# powerDist.net
KiCad netlist of a schematic drawn in EAGLE
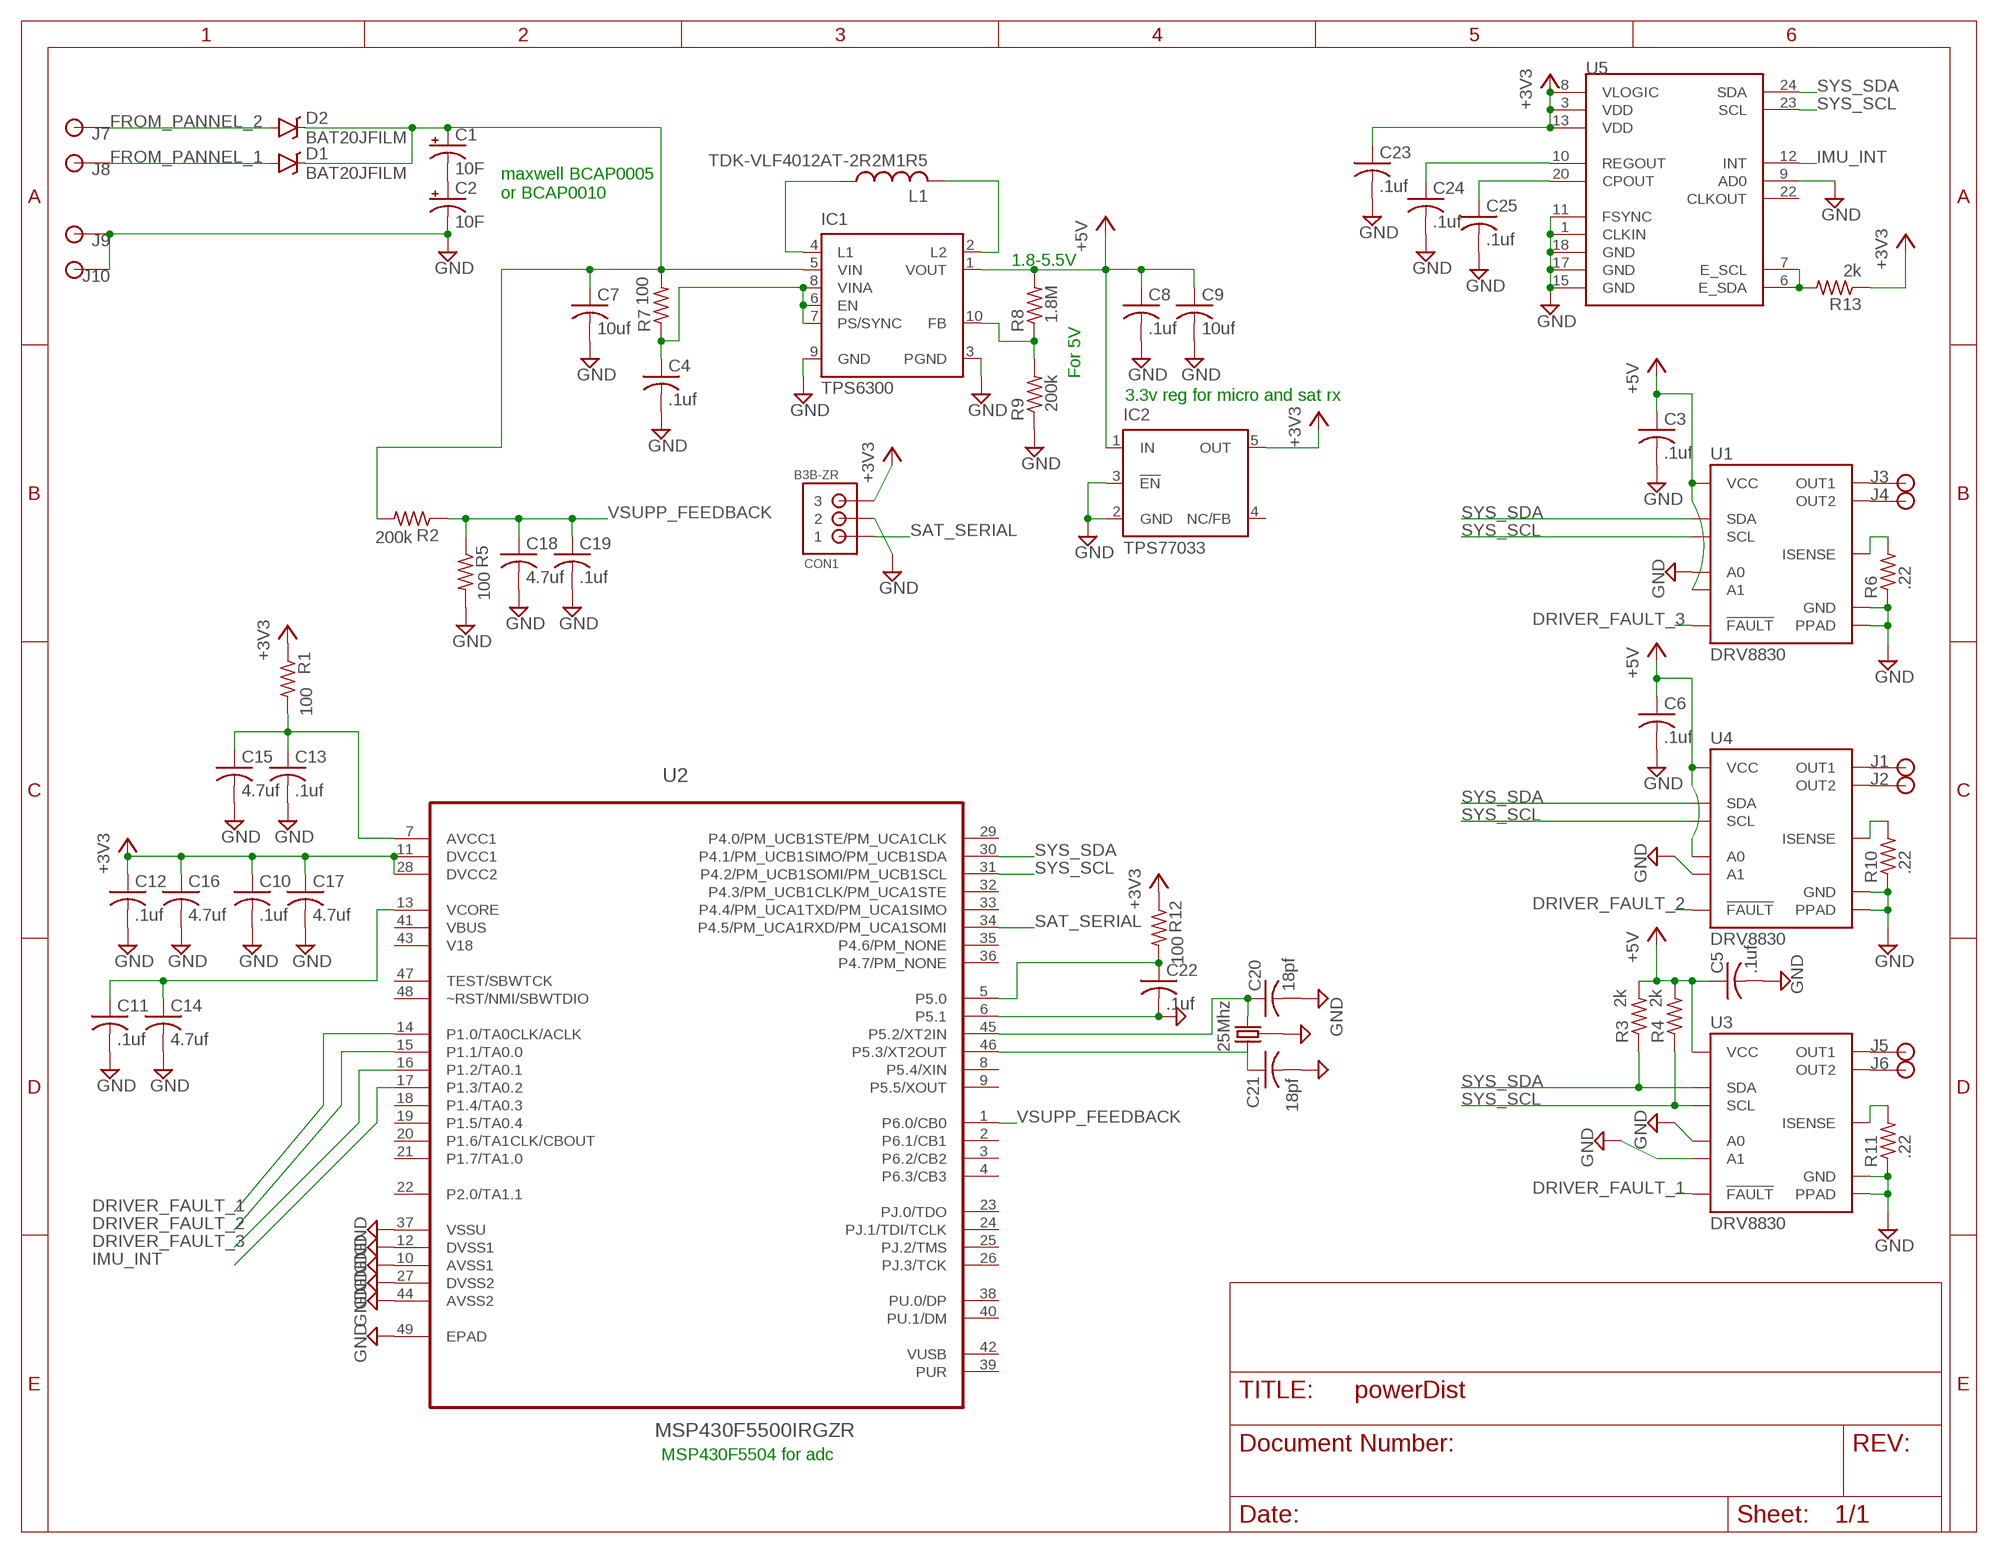
[diagram p0: schematic, sheet 1]

(export (version "E")
  (design (tool "Eeschema 10.0.6"))
  (components
    (comp (ref "C1")
      (value "10F")
      (footprint "eagle-import:E5-10,5")
      (libsource (lib "eagle-import") (part "CPOL-USE5-10.5"))
    )
    (comp (ref "C2")
      (value "10F")
      (footprint "eagle-import:E5-10,5")
      (libsource (lib "eagle-import") (part "CPOL-USE5-10.5"))
    )
    (comp (ref "C3")
      (value ".1uf")
      (footprint "eagle-import:C0603")
      (libsource (lib "eagle-import") (part "C-USC0603"))
    )
    (comp (ref "C4")
      (value ".1uf")
      (footprint "eagle-import:C0603")
      (libsource (lib "eagle-import") (part "C-USC0603"))
    )
    (comp (ref "C5")
      (value ".1uf")
      (footprint "eagle-import:C0603")
      (libsource (lib "eagle-import") (part "C-USC0603"))
    )
    (comp (ref "C6")
      (value ".1uf")
      (footprint "eagle-import:C0603")
      (libsource (lib "eagle-import") (part "C-USC0603"))
    )
    (comp (ref "C7")
      (value "10uf")
      (footprint "eagle-import:C0603")
      (libsource (lib "eagle-import") (part "C-USC0603"))
    )
    (comp (ref "C8")
      (value ".1uf")
      (footprint "eagle-import:C0603")
      (libsource (lib "eagle-import") (part "C-USC0603"))
    )
    (comp (ref "C9")
      (value "10uf")
      (footprint "eagle-import:C0603")
      (libsource (lib "eagle-import") (part "C-USC0603"))
    )
    (comp (ref "C10")
      (value ".1uf")
      (footprint "eagle-import:C0603")
      (libsource (lib "eagle-import") (part "C-USC0603"))
    )
    (comp (ref "C11")
      (value ".1uf")
      (footprint "eagle-import:C0603")
      (libsource (lib "eagle-import") (part "C-USC0603"))
    )
    (comp (ref "C12")
      (value ".1uf")
      (footprint "eagle-import:C0603")
      (libsource (lib "eagle-import") (part "C-USC0603"))
    )
    (comp (ref "C13")
      (value ".1uf")
      (footprint "eagle-import:C0603")
      (libsource (lib "eagle-import") (part "C-USC0603"))
    )
    (comp (ref "C14")
      (value "4.7uf")
      (footprint "eagle-import:C0603")
      (libsource (lib "eagle-import") (part "C-USC0603"))
    )
    (comp (ref "C15")
      (value "4.7uf")
      (footprint "eagle-import:C0603")
      (libsource (lib "eagle-import") (part "C-USC0603"))
    )
    (comp (ref "C16")
      (value "4.7uf")
      (footprint "eagle-import:C0603")
      (libsource (lib "eagle-import") (part "C-USC0603"))
    )
    (comp (ref "C17")
      (value "4.7uf")
      (footprint "eagle-import:C0603")
      (libsource (lib "eagle-import") (part "C-USC0603"))
    )
    (comp (ref "C18")
      (value "4.7uf")
      (footprint "eagle-import:C0603")
      (libsource (lib "eagle-import") (part "C-USC0603"))
    )
    (comp (ref "C19")
      (value ".1uf")
      (footprint "eagle-import:C0603")
      (libsource (lib "eagle-import") (part "C-USC0603"))
    )
    (comp (ref "C20")
      (value "18pf")
      (footprint "eagle-import:C0603")
      (libsource (lib "eagle-import") (part "C-USC0603"))
    )
    (comp (ref "C21")
      (value "18pf")
      (footprint "eagle-import:C0603")
      (libsource (lib "eagle-import") (part "C-USC0603"))
    )
    (comp (ref "C22")
      (value ".1uf")
      (footprint "eagle-import:C0603")
      (libsource (lib "eagle-import") (part "C-USC0603"))
    )
    (comp (ref "C23")
      (value ".1uf")
      (footprint "eagle-import:C0603")
      (libsource (lib "eagle-import") (part "C-USC0603"))
    )
    (comp (ref "C24")
      (value ".1uf")
      (footprint "eagle-import:C0603")
      (libsource (lib "eagle-import") (part "C-USC0603"))
    )
    (comp (ref "C25")
      (value ".1uf")
      (footprint "eagle-import:C0603")
      (libsource (lib "eagle-import") (part "C-USC0603"))
    )
    (comp (ref "CON1")
      (value "B3B-ZR")
      (footprint "eagle-import:B3B-ZR")
      (libsource (lib "eagle-import") (part "B3B-ZR"))
    )
    (comp (ref "D1")
      (value "BAT20JFILM")
      (footprint "eagle-import:SOD-323")
      (libsource (lib "eagle-import") (part "BAT20JFILM"))
    )
    (comp (ref "D2")
      (value "BAT20JFILM")
      (footprint "eagle-import:SOD-323")
      (libsource (lib "eagle-import") (part "BAT20JFILM"))
    )
    (comp (ref "IC1")
      (value "TPS6300")
      (footprint "eagle-import:DRC-S-PVSON-N10")
      (fields (field (name "MPN") "TPS63000DRCTG4"))
      (libsource (lib "eagle-import") (part "TPS6300"))
    )
    (comp (ref "IC2")
      (value "TPS77033")
      (footprint "eagle-import:SOT23-DBV")
      (fields (field (name "MF") "TEXAS INSTRUMENTS") (field (name "MPN") "TPS77033DBVT"))
      (libsource (lib "eagle-import") (part "TPS77033"))
    )
    (comp (ref "J1")
      (value "2MMPAD")
      (footprint "eagle-import:2MMPAD")
      (libsource (lib "eagle-import") (part "2MMPAD"))
    )
    (comp (ref "J2")
      (value "2MMPAD")
      (footprint "eagle-import:2MMPAD")
      (libsource (lib "eagle-import") (part "2MMPAD"))
    )
    (comp (ref "J3")
      (value "2MMPAD")
      (footprint "eagle-import:2MMPAD")
      (libsource (lib "eagle-import") (part "2MMPAD"))
    )
    (comp (ref "J4")
      (value "2MMPAD")
      (footprint "eagle-import:2MMPAD")
      (libsource (lib "eagle-import") (part "2MMPAD"))
    )
    (comp (ref "J5")
      (value "2MMPAD")
      (footprint "eagle-import:2MMPAD")
      (libsource (lib "eagle-import") (part "2MMPAD"))
    )
    (comp (ref "J6")
      (value "2MMPAD")
      (footprint "eagle-import:2MMPAD")
      (libsource (lib "eagle-import") (part "2MMPAD"))
    )
    (comp (ref "J7")
      (value "2MMPAD")
      (footprint "eagle-import:2MMPAD")
      (libsource (lib "eagle-import") (part "2MMPAD"))
    )
    (comp (ref "J8")
      (value "2MMPAD")
      (footprint "eagle-import:2MMPAD")
      (libsource (lib "eagle-import") (part "2MMPAD"))
    )
    (comp (ref "J9")
      (value "2MMPAD")
      (footprint "eagle-import:2MMPAD")
      (libsource (lib "eagle-import") (part "2MMPAD"))
    )
    (comp (ref "J10")
      (value "2MMPAD")
      (footprint "eagle-import:2MMPAD")
      (libsource (lib "eagle-import") (part "2MMPAD"))
    )
    (comp (ref "L1")
      (value "TDK-VLF4012AT-2R2M1R5")
      (footprint "eagle-import:TDK-VLF4012AT-2R2M1R5")
      (fields (field (name "MFG") "TDK"))
      (libsource (lib "eagle-import") (part "TDK-VLF4012AT-2R2M1R5"))
    )
    (comp (ref "Q1")
      (value "25Mhz")
      (footprint "eagle-import:CRYSTAL-SMD-5X3")
      (libsource (lib "eagle-import") (part "CRYSTAL-GROUNDED"))
    )
    (comp (ref "R1")
      (value "100")
      (footprint "eagle-import:R0402")
      (libsource (lib "eagle-import") (part "R-US_R0402"))
    )
    (comp (ref "R2")
      (value "200k")
      (footprint "eagle-import:R0402")
      (libsource (lib "eagle-import") (part "R-US_R0402"))
    )
    (comp (ref "R3")
      (value "2k")
      (footprint "eagle-import:R0402")
      (libsource (lib "eagle-import") (part "R-US_R0402"))
    )
    (comp (ref "R4")
      (value "2k")
      (footprint "eagle-import:R0402")
      (libsource (lib "eagle-import") (part "R-US_R0402"))
    )
    (comp (ref "R5")
      (value "100")
      (footprint "eagle-import:R0402")
      (libsource (lib "eagle-import") (part "R-US_R0402"))
    )
    (comp (ref "R6")
      (value ".22")
      (footprint "eagle-import:R0402")
      (libsource (lib "eagle-import") (part "R-US_R0402"))
    )
    (comp (ref "R7")
      (value "100")
      (footprint "eagle-import:R0402")
      (libsource (lib "eagle-import") (part "R-US_R0402"))
    )
    (comp (ref "R8")
      (value "1.8M")
      (footprint "eagle-import:R0402")
      (libsource (lib "eagle-import") (part "R-US_R0402"))
    )
    (comp (ref "R9")
      (value "200k")
      (footprint "eagle-import:R0402")
      (libsource (lib "eagle-import") (part "R-US_R0402"))
    )
    (comp (ref "R10")
      (value ".22")
      (footprint "eagle-import:R0402")
      (libsource (lib "eagle-import") (part "R-US_R0402"))
    )
    (comp (ref "R11")
      (value ".22")
      (footprint "eagle-import:R0402")
      (libsource (lib "eagle-import") (part "R-US_R0402"))
    )
    (comp (ref "R12")
      (value "100")
      (footprint "eagle-import:R0402")
      (libsource (lib "eagle-import") (part "R-US_R0402"))
    )
    (comp (ref "R13")
      (value "2k")
      (footprint "eagle-import:R0402")
      (libsource (lib "eagle-import") (part "R-US_R0402"))
    )
    (comp (ref "U1")
      (value "DRV8830")
      (footprint "eagle-import:MSOP-10-GNDPAD")
      (libsource (lib "eagle-import") (part "DRV8830"))
    )
    (comp (ref "U2")
      (value "MSP430F5500IRGZR")
      (footprint "eagle-import:QFN50P700X700X100-49N")
      (libsource (lib "eagle-import") (part "MSP430F5500IRGZR"))
    )
    (comp (ref "U3")
      (value "DRV8830")
      (footprint "eagle-import:MSOP-10-GNDPAD")
      (libsource (lib "eagle-import") (part "DRV8830"))
    )
    (comp (ref "U4")
      (value "DRV8830")
      (footprint "eagle-import:MSOP-10-GNDPAD")
      (libsource (lib "eagle-import") (part "DRV8830"))
    )
    (comp (ref "U5")
      (value "MPU-9150QFN-24-NP")
      (footprint "eagle-import:QFN-24-NP")
      (libsource (lib "eagle-import") (part "MPU-9150QFN-24-NP"))
    )
  )
  (nets
    (net (code "1") (name "+3V3") (class "Default")
      (node (ref "C10") (pin "1") (pinfunction "1_1") (pintype "passive"))
      (node (ref "C12") (pin "1") (pinfunction "1_1") (pintype "passive"))
      (node (ref "C16") (pin "1") (pinfunction "1_1") (pintype "passive"))
      (node (ref "C17") (pin "1") (pinfunction "1_1") (pintype "passive"))
      (node (ref "C23") (pin "1") (pinfunction "1_1") (pintype "passive"))
      (node (ref "CON1") (pin "3") (pinfunction "3_3") (pintype "bidirectional"))
      (node (ref "IC2") (pin "5") (pinfunction "OUT_5") (pintype "passive"))
      (node (ref "R1") (pin "1") (pinfunction "1_1") (pintype "passive"))
      (node (ref "R12") (pin "1") (pinfunction "1_1") (pintype "passive"))
      (node (ref "R13") (pin "1") (pinfunction "1_1") (pintype "passive"))
      (node (ref "U2") (pin "11") (pinfunction "DVCC1_11") (pintype "power_in"))
      (node (ref "U2") (pin "28") (pinfunction "DVCC2_28") (pintype "power_in"))
      (node (ref "U5") (pin "13") (pinfunction "VDD_13") (pintype "bidirectional"))
      (node (ref "U5") (pin "3") (pinfunction "VDD_3") (pintype "bidirectional"))
      (node (ref "U5") (pin "8") (pinfunction "VLOGIC_8") (pintype "bidirectional"))
    )
    (net (code "2") (name "+5V") (class "Default")
      (node (ref "C3") (pin "1") (pinfunction "1_1") (pintype "passive"))
      (node (ref "C5") (pin "1") (pinfunction "1_1") (pintype "passive"))
      (node (ref "C6") (pin "1") (pinfunction "1_1") (pintype "passive"))
      (node (ref "C8") (pin "1") (pinfunction "1_1") (pintype "passive"))
      (node (ref "C9") (pin "1") (pinfunction "1_1") (pintype "passive"))
      (node (ref "IC1") (pin "1") (pinfunction "VOUT_1") (pintype "output"))
      (node (ref "IC2") (pin "1") (pinfunction "IN_1") (pintype "input"))
      (node (ref "R3") (pin "2") (pinfunction "2_2") (pintype "passive"))
      (node (ref "R4") (pin "2") (pinfunction "2_2") (pintype "passive"))
      (node (ref "R8") (pin "2") (pinfunction "2_2") (pintype "passive"))
      (node (ref "U1") (pin "4") (pinfunction "VCC_4") (pintype "power_in"))
      (node (ref "U1") (pin "8") (pinfunction "A1_8") (pintype "input"))
      (node (ref "U3") (pin "4") (pinfunction "VCC_4") (pintype "power_in"))
      (node (ref "U4") (pin "4") (pinfunction "VCC_4") (pintype "power_in"))
      (node (ref "U4") (pin "7") (pinfunction "A0_7") (pintype "input"))
    )
    (net (code "3") (name "/DRIVER_FAULT_1") (class "Default")
      (node (ref "U2") (pin "14") (pinfunction "P1.0/TA0CLK/ACLK_14") (pintype "bidirectional"))
      (node (ref "U3") (pin "6") (pinfunction "~{FAULT}_6") (pintype "output"))
    )
    (net (code "4") (name "/DRIVER_FAULT_2") (class "Default")
      (node (ref "U2") (pin "15") (pinfunction "P1.1/TA0.0_15") (pintype "bidirectional"))
      (node (ref "U4") (pin "6") (pinfunction "~{FAULT}_6") (pintype "output"))
    )
    (net (code "5") (name "/DRIVER_FAULT_3") (class "Default")
      (node (ref "U1") (pin "6") (pinfunction "~{FAULT}_6") (pintype "output"))
      (node (ref "U2") (pin "16") (pinfunction "P1.2/TA0.1_16") (pintype "bidirectional"))
    )
    (net (code "6") (name "/FROM_PANNEL_1") (class "Default")
      (node (ref "D1") (pin "A") (pinfunction "A_A") (pintype "passive"))
      (node (ref "J8") (pin "P$1") (pinfunction "P$1_P$1") (pintype "bidirectional"))
    )
    (net (code "7") (name "/FROM_PANNEL_2") (class "Default")
      (node (ref "D2") (pin "A") (pinfunction "A_A") (pintype "passive"))
      (node (ref "J7") (pin "P$1") (pinfunction "P$1_P$1") (pintype "bidirectional"))
    )
    (net (code "8") (name "/IMU_INT") (class "Default")
      (node (ref "U2") (pin "17") (pinfunction "P1.3/TA0.2_17") (pintype "bidirectional"))
      (node (ref "U5") (pin "12") (pinfunction "INT_12") (pintype "bidirectional"))
    )
    (net (code "9") (name "/SAT_SERIAL") (class "Default")
      (node (ref "CON1") (pin "1") (pinfunction "1_1") (pintype "bidirectional"))
      (node (ref "U2") (pin "34") (pinfunction "P4.5/PM_UCA1RXD/PM_UCA1SOMI_34") (pintype "bidirectional"))
    )
    (net (code "10") (name "/SYS_SCL") (class "Default")
      (node (ref "R4") (pin "1") (pinfunction "1_1") (pintype "passive"))
      (node (ref "U1") (pin "10") (pinfunction "SCL_10") (pintype "input"))
      (node (ref "U2") (pin "31") (pinfunction "P4.2/PM_UCB1SOMI/PM_UCB1SCL_31") (pintype "bidirectional"))
      (node (ref "U3") (pin "10") (pinfunction "SCL_10") (pintype "input"))
      (node (ref "U4") (pin "10") (pinfunction "SCL_10") (pintype "input"))
      (node (ref "U5") (pin "23") (pinfunction "SCL_23") (pintype "bidirectional"))
    )
    (net (code "11") (name "/SYS_SDA") (class "Default")
      (node (ref "R3") (pin "1") (pinfunction "1_1") (pintype "passive"))
      (node (ref "U1") (pin "9") (pinfunction "SDA_9") (pintype "bidirectional"))
      (node (ref "U2") (pin "30") (pinfunction "P4.1/PM_UCB1SIMO/PM_UCB1SDA_30") (pintype "bidirectional"))
      (node (ref "U3") (pin "9") (pinfunction "SDA_9") (pintype "bidirectional"))
      (node (ref "U4") (pin "9") (pinfunction "SDA_9") (pintype "bidirectional"))
      (node (ref "U5") (pin "24") (pinfunction "SDA_24") (pintype "bidirectional"))
    )
    (net (code "12") (name "/V18") (class "Default")
      (node (ref "U2") (pin "43") (pinfunction "V18_43") (pintype "power_in"))
    )
    (net (code "13") (name "/VSUPP_FEEDBACK") (class "Default")
      (node (ref "C18") (pin "1") (pinfunction "1_1") (pintype "passive"))
      (node (ref "C19") (pin "1") (pinfunction "1_1") (pintype "passive"))
      (node (ref "R2") (pin "1") (pinfunction "1_1") (pintype "passive"))
      (node (ref "R5") (pin "1") (pinfunction "1_1") (pintype "passive"))
      (node (ref "U2") (pin "1") (pinfunction "P6.0/CB0_1") (pintype "bidirectional"))
    )
    (net (code "14") (name "GND") (class "Default")
      (node (ref "C10") (pin "2") (pinfunction "2_2") (pintype "passive"))
      (node (ref "C11") (pin "2") (pinfunction "2_2") (pintype "passive"))
      (node (ref "C12") (pin "2") (pinfunction "2_2") (pintype "passive"))
      (node (ref "C13") (pin "2") (pinfunction "2_2") (pintype "passive"))
      (node (ref "C14") (pin "2") (pinfunction "2_2") (pintype "passive"))
      (node (ref "C15") (pin "2") (pinfunction "2_2") (pintype "passive"))
      (node (ref "C16") (pin "2") (pinfunction "2_2") (pintype "passive"))
      (node (ref "C17") (pin "2") (pinfunction "2_2") (pintype "passive"))
      (node (ref "C18") (pin "2") (pinfunction "2_2") (pintype "passive"))
      (node (ref "C19") (pin "2") (pinfunction "2_2") (pintype "passive"))
      (node (ref "C2") (pin "-") (pinfunction "-_-") (pintype "passive"))
      (node (ref "C20") (pin "2") (pinfunction "2_2") (pintype "passive"))
      (node (ref "C21") (pin "2") (pinfunction "2_2") (pintype "passive"))
      (node (ref "C22") (pin "2") (pinfunction "2_2") (pintype "passive"))
      (node (ref "C23") (pin "2") (pinfunction "2_2") (pintype "passive"))
      (node (ref "C24") (pin "2") (pinfunction "2_2") (pintype "passive"))
      (node (ref "C25") (pin "2") (pinfunction "2_2") (pintype "passive"))
      (node (ref "C3") (pin "2") (pinfunction "2_2") (pintype "passive"))
      (node (ref "C4") (pin "2") (pinfunction "2_2") (pintype "passive"))
      (node (ref "C5") (pin "2") (pinfunction "2_2") (pintype "passive"))
      (node (ref "C6") (pin "2") (pinfunction "2_2") (pintype "passive"))
      (node (ref "C7") (pin "2") (pinfunction "2_2") (pintype "passive"))
      (node (ref "C8") (pin "2") (pinfunction "2_2") (pintype "passive"))
      (node (ref "C9") (pin "2") (pinfunction "2_2") (pintype "passive"))
      (node (ref "CON1") (pin "2") (pinfunction "2_2") (pintype "bidirectional"))
      (node (ref "IC1") (pin "3") (pinfunction "PGND_3") (pintype "power_in"))
      (node (ref "IC1") (pin "9") (pinfunction "GND_9") (pintype "power_in"))
      (node (ref "IC2") (pin "2") (pinfunction "GND_2") (pintype "power_in"))
      (node (ref "IC2") (pin "3") (pinfunction "~{EN}_3") (pintype "input"))
      (node (ref "J10") (pin "P$1") (pinfunction "P$1_P$1") (pintype "bidirectional"))
      (node (ref "J9") (pin "P$1") (pinfunction "P$1_P$1") (pintype "bidirectional"))
      (node (ref "Q1") (pin "2") (pinfunction "3_2") (pintype "passive"))
      (node (ref "Q1") (pin "4") (pinfunction "3_4") (pintype "passive"))
      (node (ref "R10") (pin "1") (pinfunction "1_1") (pintype "passive"))
      (node (ref "R11") (pin "1") (pinfunction "1_1") (pintype "passive"))
      (node (ref "R5") (pin "2") (pinfunction "2_2") (pintype "passive"))
      (node (ref "R6") (pin "1") (pinfunction "1_1") (pintype "passive"))
      (node (ref "R9") (pin "1") (pinfunction "1_1") (pintype "passive"))
      (node (ref "U1") (pin "5") (pinfunction "GND_5") (pintype "power_in"))
      (node (ref "U1") (pin "7") (pinfunction "A0_7") (pintype "input"))
      (node (ref "U1") (pin "GND") (pinfunction "PPAD_GND") (pintype "power_in"))
      (node (ref "U2") (pin "10") (pinfunction "AVSS1_10") (pintype "power_in"))
      (node (ref "U2") (pin "12") (pinfunction "DVSS1_12") (pintype "power_in"))
      (node (ref "U2") (pin "27") (pinfunction "DVSS2_27") (pintype "power_in"))
      (node (ref "U2") (pin "37") (pinfunction "VSSU_37") (pintype "power_in"))
      (node (ref "U2") (pin "44") (pinfunction "AVSS2_44") (pintype "power_in"))
      (node (ref "U2") (pin "49") (pinfunction "EPAD_49") (pintype "passive"))
      (node (ref "U2") (pin "6") (pinfunction "P5.1_6") (pintype "bidirectional"))
      (node (ref "U3") (pin "5") (pinfunction "GND_5") (pintype "power_in"))
      (node (ref "U3") (pin "7") (pinfunction "A0_7") (pintype "input"))
      (node (ref "U3") (pin "8") (pinfunction "A1_8") (pintype "input"))
      (node (ref "U3") (pin "GND") (pinfunction "PPAD_GND") (pintype "power_in"))
      (node (ref "U4") (pin "5") (pinfunction "GND_5") (pintype "power_in"))
      (node (ref "U4") (pin "8") (pinfunction "A1_8") (pintype "input"))
      (node (ref "U4") (pin "GND") (pinfunction "PPAD_GND") (pintype "power_in"))
      (node (ref "U5") (pin "1") (pinfunction "CLKIN_1") (pintype "bidirectional"))
      (node (ref "U5") (pin "11") (pinfunction "FSYNC_11") (pintype "bidirectional"))
      (node (ref "U5") (pin "15") (pinfunction "GND_15") (pintype "bidirectional"))
      (node (ref "U5") (pin "17") (pinfunction "GND_17") (pintype "bidirectional"))
      (node (ref "U5") (pin "18") (pinfunction "GND_18") (pintype "bidirectional"))
      (node (ref "U5") (pin "9") (pinfunction "AD0_9") (pintype "bidirectional"))
    )
    (net (code "15") (name "Net-(C1-Pad-)") (class "Default")
      (node (ref "C1") (pin "-") (pinfunction "-_-") (pintype "passive"))
      (node (ref "C2") (pin "+") (pinfunction "+_+") (pintype "passive"))
    )
    (net (code "16") (name "Net-(IC1A-EN)") (class "Default")
      (node (ref "C4") (pin "1") (pinfunction "1_1") (pintype "passive"))
      (node (ref "IC1") (pin "6") (pinfunction "EN_6") (pintype "input"))
      (node (ref "IC1") (pin "7") (pinfunction "PS/SYNC_7") (pintype "input"))
      (node (ref "IC1") (pin "8") (pinfunction "VINA_8") (pintype "input"))
      (node (ref "R7") (pin "1") (pinfunction "1_1") (pintype "passive"))
    )
    (net (code "17") (name "Net-(IC1A-FB)") (class "Default")
      (node (ref "IC1") (pin "10") (pinfunction "FB_10") (pintype "input"))
      (node (ref "R8") (pin "1") (pinfunction "1_1") (pintype "passive"))
      (node (ref "R9") (pin "2") (pinfunction "2_2") (pintype "passive"))
    )
    (net (code "18") (name "Net-(IC1A-L1)") (class "Default")
      (node (ref "IC1") (pin "4") (pinfunction "L1_4") (pintype "passive"))
      (node (ref "L1") (pin "P$1") (pinfunction "1_P$1") (pintype "passive"))
    )
    (net (code "19") (name "Net-(IC1A-L2)") (class "Default")
      (node (ref "IC1") (pin "2") (pinfunction "L2_2") (pintype "passive"))
      (node (ref "L1") (pin "P$2") (pinfunction "2_P$2") (pintype "passive"))
    )
    (net (code "20") (name "Net-(IC1A-VIN)") (class "Default")
      (node (ref "C1") (pin "+") (pinfunction "+_+") (pintype "passive"))
      (node (ref "C7") (pin "1") (pinfunction "1_1") (pintype "passive"))
      (node (ref "D1") (pin "C") (pinfunction "C_C") (pintype "passive"))
      (node (ref "D2") (pin "C") (pinfunction "C_C") (pintype "passive"))
      (node (ref "IC1") (pin "5") (pinfunction "VIN_5") (pintype "input"))
      (node (ref "R2") (pin "2") (pinfunction "2_2") (pintype "passive"))
      (node (ref "R7") (pin "2") (pinfunction "2_2") (pintype "passive"))
    )
    (net (code "21") (name "Net-(Q1-1)") (class "Default")
      (node (ref "C21") (pin "1") (pinfunction "1_1") (pintype "passive"))
      (node (ref "Q1") (pin "3") (pinfunction "1_3") (pintype "passive"))
      (node (ref "U2") (pin "46") (pinfunction "P5.3/XT2OUT_46") (pintype "bidirectional"))
    )
    (net (code "22") (name "Net-(Q1-2)") (class "Default")
      (node (ref "C20") (pin "1") (pinfunction "1_1") (pintype "passive"))
      (node (ref "Q1") (pin "1") (pinfunction "2_1") (pintype "passive"))
      (node (ref "U2") (pin "45") (pinfunction "P5.2/XT2IN_45") (pintype "bidirectional"))
    )
    (net (code "23") (name "Net-(U1-ISENSE)") (class "Default")
      (node (ref "R6") (pin "2") (pinfunction "2_2") (pintype "passive"))
      (node (ref "U1") (pin "2") (pinfunction "ISENSE_2") (pintype "bidirectional"))
    )
    (net (code "24") (name "Net-(U1-OUT1)") (class "Default")
      (node (ref "J3") (pin "P$1") (pinfunction "P$1_P$1") (pintype "bidirectional"))
      (node (ref "U1") (pin "3") (pinfunction "OUT1_3") (pintype "power_in"))
    )
    (net (code "25") (name "Net-(U1-OUT2)") (class "Default")
      (node (ref "J4") (pin "P$1") (pinfunction "P$1_P$1") (pintype "bidirectional"))
      (node (ref "U1") (pin "1") (pinfunction "OUT2_1") (pintype "power_in"))
    )
    (net (code "26") (name "Net-(U2-AVCC1)") (class "Default")
      (node (ref "C13") (pin "1") (pinfunction "1_1") (pintype "passive"))
      (node (ref "C15") (pin "1") (pinfunction "1_1") (pintype "passive"))
      (node (ref "R1") (pin "2") (pinfunction "2_2") (pintype "passive"))
      (node (ref "U2") (pin "7") (pinfunction "AVCC1_7") (pintype "power_in"))
    )
    (net (code "27") (name "Net-(U2-P5.0)") (class "Default")
      (node (ref "C22") (pin "1") (pinfunction "1_1") (pintype "passive"))
      (node (ref "R12") (pin "2") (pinfunction "2_2") (pintype "passive"))
      (node (ref "U2") (pin "5") (pinfunction "P5.0_5") (pintype "bidirectional"))
    )
    (net (code "28") (name "Net-(U2-VCORE)") (class "Default")
      (node (ref "C11") (pin "1") (pinfunction "1_1") (pintype "passive"))
      (node (ref "C14") (pin "1") (pinfunction "1_1") (pintype "passive"))
      (node (ref "U2") (pin "13") (pinfunction "VCORE_13") (pintype "power_in"))
    )
    (net (code "29") (name "Net-(U3-ISENSE)") (class "Default")
      (node (ref "R11") (pin "2") (pinfunction "2_2") (pintype "passive"))
      (node (ref "U3") (pin "2") (pinfunction "ISENSE_2") (pintype "bidirectional"))
    )
    (net (code "30") (name "Net-(U3-OUT1)") (class "Default")
      (node (ref "J5") (pin "P$1") (pinfunction "P$1_P$1") (pintype "bidirectional"))
      (node (ref "U3") (pin "3") (pinfunction "OUT1_3") (pintype "power_in"))
    )
    (net (code "31") (name "Net-(U3-OUT2)") (class "Default")
      (node (ref "J6") (pin "P$1") (pinfunction "P$1_P$1") (pintype "bidirectional"))
      (node (ref "U3") (pin "1") (pinfunction "OUT2_1") (pintype "power_in"))
    )
    (net (code "32") (name "Net-(U4-ISENSE)") (class "Default")
      (node (ref "R10") (pin "2") (pinfunction "2_2") (pintype "passive"))
      (node (ref "U4") (pin "2") (pinfunction "ISENSE_2") (pintype "bidirectional"))
    )
    (net (code "33") (name "Net-(U4-OUT1)") (class "Default")
      (node (ref "J1") (pin "P$1") (pinfunction "P$1_P$1") (pintype "bidirectional"))
      (node (ref "U4") (pin "3") (pinfunction "OUT1_3") (pintype "power_in"))
    )
    (net (code "34") (name "Net-(U4-OUT2)") (class "Default")
      (node (ref "J2") (pin "P$1") (pinfunction "P$1_P$1") (pintype "bidirectional"))
      (node (ref "U4") (pin "1") (pinfunction "OUT2_1") (pintype "power_in"))
    )
    (net (code "35") (name "Net-(U5-CPOUT)") (class "Default")
      (node (ref "C25") (pin "1") (pinfunction "1_1") (pintype "passive"))
      (node (ref "U5") (pin "20") (pinfunction "CPOUT_20") (pintype "bidirectional"))
    )
    (net (code "36") (name "Net-(U5-E_SCL)") (class "Default")
      (node (ref "R13") (pin "2") (pinfunction "2_2") (pintype "passive"))
      (node (ref "U5") (pin "6") (pinfunction "E_SDA_6") (pintype "bidirectional"))
      (node (ref "U5") (pin "7") (pinfunction "E_SCL_7") (pintype "bidirectional"))
    )
    (net (code "37") (name "Net-(U5-REGOUT)") (class "Default")
      (node (ref "C24") (pin "1") (pinfunction "1_1") (pintype "passive"))
      (node (ref "U5") (pin "10") (pinfunction "REGOUT_10") (pintype "bidirectional"))
    )
    (net (code "38") (name "unconnected-(IC2-NC{slash}FB-Pad4)") (class "Default")
      (node (ref "IC2") (pin "4") (pinfunction "NC/FB_4") (pintype "passive"))
    )
    (net (code "39") (name "unconnected-(U2-P1.4{slash}TA0.3-Pad18)") (class "Default")
      (node (ref "U2") (pin "18") (pinfunction "P1.4/TA0.3_18") (pintype "bidirectional"))
    )
    (net (code "40") (name "unconnected-(U2-P1.5{slash}TA0.4-Pad19)") (class "Default")
      (node (ref "U2") (pin "19") (pinfunction "P1.5/TA0.4_19") (pintype "bidirectional"))
    )
    (net (code "41") (name "unconnected-(U2-P1.6{slash}TA1CLK{slash}CBOUT-Pad20)") (class "Default")
      (node (ref "U2") (pin "20") (pinfunction "P1.6/TA1CLK/CBOUT_20") (pintype "bidirectional"))
    )
    (net (code "42") (name "unconnected-(U2-P1.7{slash}TA1.0-Pad21)") (class "Default")
      (node (ref "U2") (pin "21") (pinfunction "P1.7/TA1.0_21") (pintype "bidirectional"))
    )
    (net (code "43") (name "unconnected-(U2-P2.0{slash}TA1.1-Pad22)") (class "Default")
      (node (ref "U2") (pin "22") (pinfunction "P2.0/TA1.1_22") (pintype "bidirectional"))
    )
    (net (code "44") (name "unconnected-(U2-P4.0{slash}PM_UCB1STE{slash}PM_UCA1CLK-Pad29)") (class "Default")
      (node (ref "U2") (pin "29") (pinfunction "P4.0/PM_UCB1STE/PM_UCA1CLK_29") (pintype "bidirectional"))
    )
    (net (code "45") (name "unconnected-(U2-P4.3{slash}PM_UCB1CLK{slash}PM_UCA1STE-Pad32)") (class "Default")
      (node (ref "U2") (pin "32") (pinfunction "P4.3/PM_UCB1CLK/PM_UCA1STE_32") (pintype "bidirectional"))
    )
    (net (code "46") (name "unconnected-(U2-P4.4{slash}PM_UCA1TXD{slash}PM_UCA1SIMO-Pad33)") (class "Default")
      (node (ref "U2") (pin "33") (pinfunction "P4.4/PM_UCA1TXD/PM_UCA1SIMO_33") (pintype "bidirectional"))
    )
    (net (code "47") (name "unconnected-(U2-P4.6{slash}PM_NONE-Pad35)") (class "Default")
      (node (ref "U2") (pin "35") (pinfunction "P4.6/PM_NONE_35") (pintype "bidirectional"))
    )
    (net (code "48") (name "unconnected-(U2-P4.7{slash}PM_NONE-Pad36)") (class "Default")
      (node (ref "U2") (pin "36") (pinfunction "P4.7/PM_NONE_36") (pintype "bidirectional"))
    )
    (net (code "49") (name "unconnected-(U2-P5.4{slash}XIN-Pad8)") (class "Default")
      (node (ref "U2") (pin "8") (pinfunction "P5.4/XIN_8") (pintype "bidirectional"))
    )
    (net (code "50") (name "unconnected-(U2-P5.5{slash}XOUT-Pad9)") (class "Default")
      (node (ref "U2") (pin "9") (pinfunction "P5.5/XOUT_9") (pintype "bidirectional"))
    )
    (net (code "51") (name "unconnected-(U2-P6.1{slash}CB1-Pad2)") (class "Default")
      (node (ref "U2") (pin "2") (pinfunction "P6.1/CB1_2") (pintype "bidirectional"))
    )
    (net (code "52") (name "unconnected-(U2-P6.2{slash}CB2-Pad3)") (class "Default")
      (node (ref "U2") (pin "3") (pinfunction "P6.2/CB2_3") (pintype "bidirectional"))
    )
    (net (code "53") (name "unconnected-(U2-P6.3{slash}CB3-Pad4)") (class "Default")
      (node (ref "U2") (pin "4") (pinfunction "P6.3/CB3_4") (pintype "bidirectional"))
    )
    (net (code "54") (name "unconnected-(U2-PJ.0{slash}TDO-Pad23)") (class "Default")
      (node (ref "U2") (pin "23") (pinfunction "PJ.0/TDO_23") (pintype "bidirectional"))
    )
    (net (code "55") (name "unconnected-(U2-PJ.1{slash}TDI{slash}TCLK-Pad24)") (class "Default")
      (node (ref "U2") (pin "24") (pinfunction "PJ.1/TDI/TCLK_24") (pintype "bidirectional"))
    )
    (net (code "56") (name "unconnected-(U2-PJ.2{slash}TMS-Pad25)") (class "Default")
      (node (ref "U2") (pin "25") (pinfunction "PJ.2/TMS_25") (pintype "bidirectional"))
    )
    (net (code "57") (name "unconnected-(U2-PJ.3{slash}TCK-Pad26)") (class "Default")
      (node (ref "U2") (pin "26") (pinfunction "PJ.3/TCK_26") (pintype "bidirectional"))
    )
    (net (code "58") (name "unconnected-(U2-PU.0{slash}DP-Pad38)") (class "Default")
      (node (ref "U2") (pin "38") (pinfunction "PU.0/DP_38") (pintype "bidirectional"))
    )
    (net (code "59") (name "unconnected-(U2-PU.1{slash}DM-Pad40)") (class "Default")
      (node (ref "U2") (pin "40") (pinfunction "PU.1/DM_40") (pintype "bidirectional"))
    )
    (net (code "60") (name "unconnected-(U2-PUR-Pad39)") (class "Default")
      (node (ref "U2") (pin "39") (pinfunction "PUR_39") (pintype "bidirectional"))
    )
    (net (code "61") (name "unconnected-(U2-TEST{slash}SBWTCK-Pad47)") (class "Default")
      (node (ref "U2") (pin "47") (pinfunction "TEST/SBWTCK_47") (pintype "input"))
    )
    (net (code "62") (name "unconnected-(U2-VBUS-Pad41)") (class "Default")
      (node (ref "U2") (pin "41") (pinfunction "VBUS_41") (pintype "input"))
    )
    (net (code "63") (name "unconnected-(U2-VUSB-Pad42)") (class "Default")
      (node (ref "U2") (pin "42") (pinfunction "VUSB_42") (pintype "output"))
    )
    (net (code "64") (name "unconnected-(U2-~{RST{slash}NMI{slash}SBWTDIO}-Pad48)") (class "Default")
      (node (ref "U2") (pin "48") (pinfunction "~{RST/NMI/SBWTDIO}_48") (pintype "bidirectional"))
    )
    (net (code "65") (name "unconnected-(U5-CLKOUT-Pad22)") (class "Default")
      (node (ref "U5") (pin "22") (pinfunction "CLKOUT_22") (pintype "bidirectional"))
    )
  )
)
